# Motherboard_1.net
KiCad netlist of a schematic drawn in EAGLE
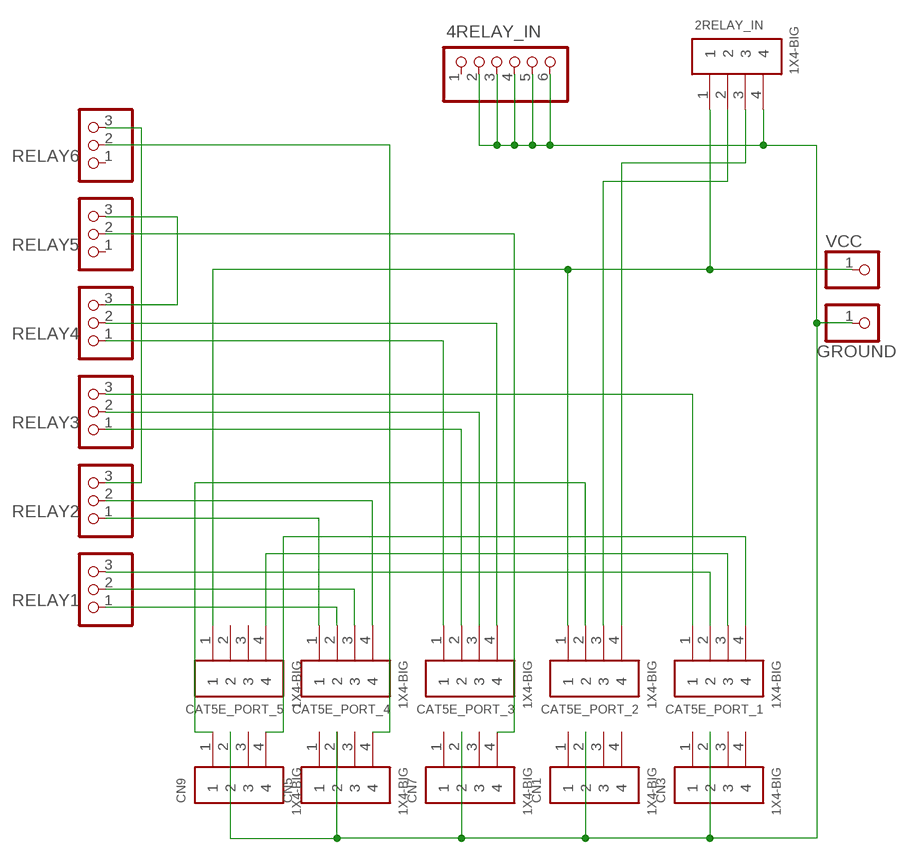
[diagram p0: schematic, sheet 1]

(export (version "E")
  (design (tool "Eeschema 10.0.6"))
  (components
    (comp (ref "2RELAY_IN")
      (value "1X4-BIG")
      (footprint "eagle-import:1X04-BIG")
      (libsource (lib "eagle-import") (part "1X4-BIG"))
    )
    (comp (ref "4RELAY_IN")
      (value "PINHD-1X6")
      (footprint "eagle-import:1X06")
      (libsource (lib "eagle-import") (part "PINHD-1X6"))
    )
    (comp (ref "CAT5E_PORT_1")
      (value "1X4-BIG")
      (footprint "eagle-import:1X04-BIG")
      (libsource (lib "eagle-import") (part "1X4-BIG"))
    )
    (comp (ref "CAT5E_PORT_2")
      (value "1X4-BIG")
      (footprint "eagle-import:1X04-BIG")
      (libsource (lib "eagle-import") (part "1X4-BIG"))
    )
    (comp (ref "CAT5E_PORT_3")
      (value "1X4-BIG")
      (footprint "eagle-import:1X04-BIG")
      (libsource (lib "eagle-import") (part "1X4-BIG"))
    )
    (comp (ref "CAT5E_PORT_4")
      (value "1X4-BIG")
      (footprint "eagle-import:1X04-BIG")
      (libsource (lib "eagle-import") (part "1X4-BIG"))
    )
    (comp (ref "CAT5E_PORT_5")
      (value "1X4-BIG")
      (footprint "eagle-import:1X04-BIG")
      (libsource (lib "eagle-import") (part "1X4-BIG"))
    )
    (comp (ref "CN1")
      (value "1X4-BIG")
      (footprint "eagle-import:1X04-BIG")
      (libsource (lib "eagle-import") (part "1X4-BIG"))
    )
    (comp (ref "CN3")
      (value "1X4-BIG")
      (footprint "eagle-import:1X04-BIG")
      (libsource (lib "eagle-import") (part "1X4-BIG"))
    )
    (comp (ref "CN5")
      (value "1X4-BIG")
      (footprint "eagle-import:1X04-BIG")
      (libsource (lib "eagle-import") (part "1X4-BIG"))
    )
    (comp (ref "CN7")
      (value "1X4-BIG")
      (footprint "eagle-import:1X04-BIG")
      (libsource (lib "eagle-import") (part "1X4-BIG"))
    )
    (comp (ref "CN9")
      (value "1X4-BIG")
      (footprint "eagle-import:1X04-BIG")
      (libsource (lib "eagle-import") (part "1X4-BIG"))
    )
    (comp (ref "GROUND")
      (value "PINHD-1X1")
      (footprint "eagle-import:1X01")
      (libsource (lib "eagle-import") (part "PINHD-1X1"))
    )
    (comp (ref "RELAY1")
      (value "PINHD-1X3")
      (footprint "eagle-import:1X03")
      (libsource (lib "eagle-import") (part "PINHD-1X3"))
    )
    (comp (ref "RELAY2")
      (value "PINHD-1X3")
      (footprint "eagle-import:1X03")
      (libsource (lib "eagle-import") (part "PINHD-1X3"))
    )
    (comp (ref "RELAY3")
      (value "PINHD-1X3")
      (footprint "eagle-import:1X03")
      (libsource (lib "eagle-import") (part "PINHD-1X3"))
    )
    (comp (ref "RELAY4")
      (value "PINHD-1X3")
      (footprint "eagle-import:1X03")
      (libsource (lib "eagle-import") (part "PINHD-1X3"))
    )
    (comp (ref "RELAY5")
      (value "PINHD-1X3")
      (footprint "eagle-import:1X03")
      (libsource (lib "eagle-import") (part "PINHD-1X3"))
    )
    (comp (ref "RELAY6")
      (value "PINHD-1X3")
      (footprint "eagle-import:1X03")
      (libsource (lib "eagle-import") (part "PINHD-1X3"))
    )
    (comp (ref "VCC")
      (value "PINHD-1X1")
      (footprint "eagle-import:1X01")
      (libsource (lib "eagle-import") (part "PINHD-1X1"))
    )
  )
  (nets
    (net (code "1") (name "Net-(2RELAY_IN-Pad1)") (class "Default")
      (node (ref "2RELAY_IN") (pin "1") (pinfunction "1_1") (pintype "bidirectional"))
      (node (ref "CAT5E_PORT_2") (pin "1") (pinfunction "1_1") (pintype "bidirectional"))
      (node (ref "CAT5E_PORT_5") (pin "1") (pinfunction "1_1") (pintype "bidirectional"))
      (node (ref "VCC") (pin "1") (pinfunction "1_1") (pintype "passive"))
    )
    (net (code "2") (name "Net-(2RELAY_IN-Pad2)") (class "Default")
      (node (ref "2RELAY_IN") (pin "2") (pinfunction "2_2") (pintype "bidirectional"))
      (node (ref "CAT5E_PORT_2") (pin "3") (pinfunction "3_3") (pintype "bidirectional"))
    )
    (net (code "3") (name "Net-(2RELAY_IN-Pad3)") (class "Default")
      (node (ref "2RELAY_IN") (pin "3") (pinfunction "3_3") (pintype "bidirectional"))
      (node (ref "CAT5E_PORT_2") (pin "4") (pinfunction "4_4") (pintype "bidirectional"))
    )
    (net (code "4") (name "Net-(2RELAY_IN-Pad4)") (class "Default")
      (node (ref "2RELAY_IN") (pin "4") (pinfunction "4_4") (pintype "bidirectional"))
      (node (ref "4RELAY_IN") (pin "2") (pinfunction "2_2") (pintype "passive"))
      (node (ref "4RELAY_IN") (pin "3") (pinfunction "3_3") (pintype "passive"))
      (node (ref "4RELAY_IN") (pin "4") (pinfunction "4_4") (pintype "passive"))
      (node (ref "4RELAY_IN") (pin "5") (pinfunction "5_5") (pintype "passive"))
      (node (ref "4RELAY_IN") (pin "6") (pinfunction "6_6") (pintype "passive"))
      (node (ref "CN1") (pin "2") (pinfunction "2_2") (pintype "bidirectional"))
      (node (ref "CN3") (pin "2") (pinfunction "2_2") (pintype "bidirectional"))
      (node (ref "CN5") (pin "2") (pinfunction "2_2") (pintype "bidirectional"))
      (node (ref "CN7") (pin "2") (pinfunction "2_2") (pintype "bidirectional"))
      (node (ref "CN9") (pin "2") (pinfunction "2_2") (pintype "bidirectional"))
      (node (ref "GROUND") (pin "1") (pinfunction "1_1") (pintype "passive"))
    )
    (net (code "5") (name "Net-(CAT5E_PORT_1-Pad1)") (class "Default")
      (node (ref "CAT5E_PORT_1") (pin "1") (pinfunction "1_1") (pintype "bidirectional"))
      (node (ref "RELAY3") (pin "3") (pinfunction "3_3") (pintype "passive"))
    )
    (net (code "6") (name "Net-(CAT5E_PORT_1-Pad2)") (class "Default")
      (node (ref "CAT5E_PORT_1") (pin "2") (pinfunction "2_2") (pintype "bidirectional"))
      (node (ref "RELAY1") (pin "3") (pinfunction "3_3") (pintype "passive"))
    )
    (net (code "7") (name "Net-(CAT5E_PORT_1-Pad3)") (class "Default")
      (node (ref "CAT5E_PORT_1") (pin "3") (pinfunction "3_3") (pintype "bidirectional"))
      (node (ref "CAT5E_PORT_5") (pin "4") (pinfunction "4_4") (pintype "bidirectional"))
    )
    (net (code "8") (name "Net-(CAT5E_PORT_1-Pad4)") (class "Default")
      (node (ref "CAT5E_PORT_1") (pin "4") (pinfunction "4_4") (pintype "bidirectional"))
      (node (ref "CN9") (pin "4") (pinfunction "4_4") (pintype "bidirectional"))
    )
    (net (code "9") (name "Net-(CAT5E_PORT_2-Pad2)") (class "Default")
      (node (ref "CAT5E_PORT_2") (pin "2") (pinfunction "2_2") (pintype "bidirectional"))
      (node (ref "CN9") (pin "1") (pinfunction "1_1") (pintype "bidirectional"))
    )
    (net (code "10") (name "Net-(CAT5E_PORT_3-Pad1)") (class "Default")
      (node (ref "CAT5E_PORT_3") (pin "1") (pinfunction "1_1") (pintype "bidirectional"))
      (node (ref "RELAY4") (pin "1") (pinfunction "1_1") (pintype "passive"))
    )
    (net (code "11") (name "Net-(CAT5E_PORT_3-Pad2)") (class "Default")
      (node (ref "CAT5E_PORT_3") (pin "2") (pinfunction "2_2") (pintype "bidirectional"))
      (node (ref "RELAY3") (pin "1") (pinfunction "1_1") (pintype "passive"))
    )
    (net (code "12") (name "Net-(CAT5E_PORT_3-Pad3)") (class "Default")
      (node (ref "CAT5E_PORT_3") (pin "3") (pinfunction "3_3") (pintype "bidirectional"))
      (node (ref "RELAY3") (pin "2") (pinfunction "2_2") (pintype "passive"))
    )
    (net (code "13") (name "Net-(CAT5E_PORT_3-Pad4)") (class "Default")
      (node (ref "CAT5E_PORT_3") (pin "4") (pinfunction "4_4") (pintype "bidirectional"))
      (node (ref "RELAY4") (pin "2") (pinfunction "2_2") (pintype "passive"))
    )
    (net (code "14") (name "Net-(CAT5E_PORT_4-Pad1)") (class "Default")
      (node (ref "CAT5E_PORT_4") (pin "1") (pinfunction "1_1") (pintype "bidirectional"))
      (node (ref "RELAY2") (pin "1") (pinfunction "1_1") (pintype "passive"))
    )
    (net (code "15") (name "Net-(CAT5E_PORT_4-Pad2)") (class "Default")
      (node (ref "CAT5E_PORT_4") (pin "2") (pinfunction "2_2") (pintype "bidirectional"))
      (node (ref "RELAY1") (pin "1") (pinfunction "1_1") (pintype "passive"))
    )
    (net (code "16") (name "Net-(CAT5E_PORT_4-Pad3)") (class "Default")
      (node (ref "CAT5E_PORT_4") (pin "3") (pinfunction "3_3") (pintype "bidirectional"))
      (node (ref "RELAY1") (pin "2") (pinfunction "2_2") (pintype "passive"))
    )
    (net (code "17") (name "Net-(CAT5E_PORT_4-Pad4)") (class "Default")
      (node (ref "CAT5E_PORT_4") (pin "4") (pinfunction "4_4") (pintype "bidirectional"))
      (node (ref "RELAY2") (pin "2") (pinfunction "2_2") (pintype "passive"))
    )
    (net (code "18") (name "Net-(CN5-Pad4)") (class "Default")
      (node (ref "CN5") (pin "4") (pinfunction "4_4") (pintype "bidirectional"))
      (node (ref "RELAY6") (pin "2") (pinfunction "2_2") (pintype "passive"))
    )
    (net (code "19") (name "Net-(CN7-Pad4)") (class "Default")
      (node (ref "CN7") (pin "4") (pinfunction "4_4") (pintype "bidirectional"))
      (node (ref "RELAY5") (pin "2") (pinfunction "2_2") (pintype "passive"))
    )
    (net (code "20") (name "Net-(RELAY2-Pad3)") (class "Default")
      (node (ref "RELAY2") (pin "3") (pinfunction "3_3") (pintype "passive"))
      (node (ref "RELAY6") (pin "3") (pinfunction "3_3") (pintype "passive"))
    )
    (net (code "21") (name "Net-(RELAY4-Pad3)") (class "Default")
      (node (ref "RELAY4") (pin "3") (pinfunction "3_3") (pintype "passive"))
      (node (ref "RELAY5") (pin "3") (pinfunction "3_3") (pintype "passive"))
    )
    (net (code "22") (name "unconnected-(4RELAY_IN-Pad1)") (class "Default")
      (node (ref "4RELAY_IN") (pin "1") (pinfunction "1_1") (pintype "passive"))
    )
    (net (code "23") (name "unconnected-(CAT5E_PORT_5-Pad2)") (class "Default")
      (node (ref "CAT5E_PORT_5") (pin "2") (pinfunction "2_2") (pintype "bidirectional"))
    )
    (net (code "24") (name "unconnected-(CAT5E_PORT_5-Pad3)") (class "Default")
      (node (ref "CAT5E_PORT_5") (pin "3") (pinfunction "3_3") (pintype "bidirectional"))
    )
    (net (code "25") (name "unconnected-(CN1-Pad1)") (class "Default")
      (node (ref "CN1") (pin "1") (pinfunction "1_1") (pintype "bidirectional"))
    )
    (net (code "26") (name "unconnected-(CN1-Pad3)") (class "Default")
      (node (ref "CN1") (pin "3") (pinfunction "3_3") (pintype "bidirectional"))
    )
    (net (code "27") (name "unconnected-(CN1-Pad4)") (class "Default")
      (node (ref "CN1") (pin "4") (pinfunction "4_4") (pintype "bidirectional"))
    )
    (net (code "28") (name "unconnected-(CN3-Pad1)") (class "Default")
      (node (ref "CN3") (pin "1") (pinfunction "1_1") (pintype "bidirectional"))
    )
    (net (code "29") (name "unconnected-(CN3-Pad3)") (class "Default")
      (node (ref "CN3") (pin "3") (pinfunction "3_3") (pintype "bidirectional"))
    )
    (net (code "30") (name "unconnected-(CN3-Pad4)") (class "Default")
      (node (ref "CN3") (pin "4") (pinfunction "4_4") (pintype "bidirectional"))
    )
    (net (code "31") (name "unconnected-(CN5-Pad1)") (class "Default")
      (node (ref "CN5") (pin "1") (pinfunction "1_1") (pintype "bidirectional"))
    )
    (net (code "32") (name "unconnected-(CN5-Pad3)") (class "Default")
      (node (ref "CN5") (pin "3") (pinfunction "3_3") (pintype "bidirectional"))
    )
    (net (code "33") (name "unconnected-(CN7-Pad1)") (class "Default")
      (node (ref "CN7") (pin "1") (pinfunction "1_1") (pintype "bidirectional"))
    )
    (net (code "34") (name "unconnected-(CN7-Pad3)") (class "Default")
      (node (ref "CN7") (pin "3") (pinfunction "3_3") (pintype "bidirectional"))
    )
    (net (code "35") (name "unconnected-(CN9-Pad3)") (class "Default")
      (node (ref "CN9") (pin "3") (pinfunction "3_3") (pintype "bidirectional"))
    )
    (net (code "36") (name "unconnected-(RELAY5-Pad1)") (class "Default")
      (node (ref "RELAY5") (pin "1") (pinfunction "1_1") (pintype "passive"))
    )
    (net (code "37") (name "unconnected-(RELAY6-Pad1)") (class "Default")
      (node (ref "RELAY6") (pin "1") (pinfunction "1_1") (pintype "passive"))
    )
  )
)
